# charger.net
KiCad netlist of a schematic drawn in EAGLE
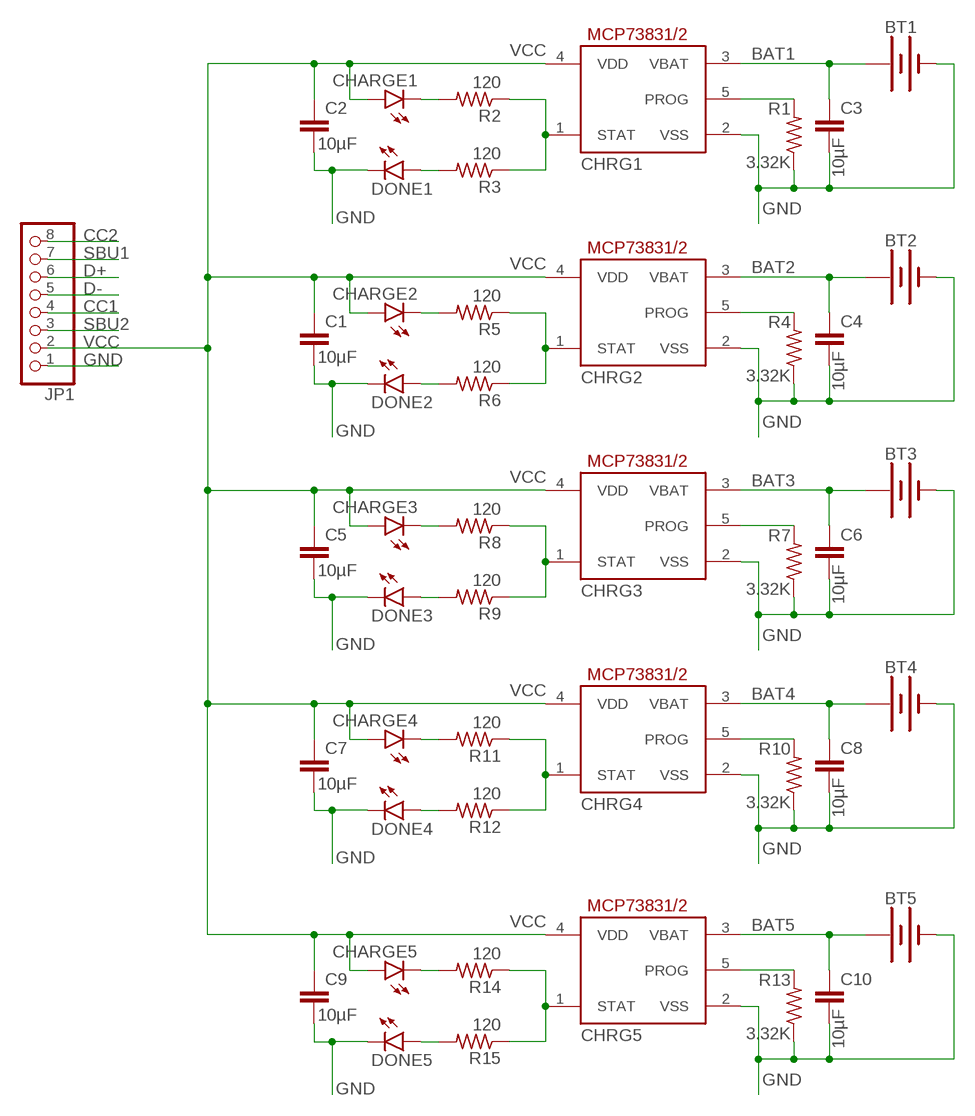
[diagram p0: schematic, sheet 1]

(export (version "E")
  (design (tool "Eeschema 10.0.6"))
  (components
    (comp (ref "BT1")
      (value "BATTERY-18650")
      (footprint "eagle-import:BATTERY_18650-HOLDER")
      (libsource (lib "eagle-import") (part "BATTERY-18650"))
    )
    (comp (ref "BT2")
      (value "BATTERY-18650")
      (footprint "eagle-import:BATTERY_18650-HOLDER")
      (libsource (lib "eagle-import") (part "BATTERY-18650"))
    )
    (comp (ref "BT3")
      (value "BATTERY-18650")
      (footprint "eagle-import:BATTERY_18650-HOLDER")
      (libsource (lib "eagle-import") (part "BATTERY-18650"))
    )
    (comp (ref "BT4")
      (value "BATTERY-18650")
      (footprint "eagle-import:BATTERY_18650-HOLDER")
      (libsource (lib "eagle-import") (part "BATTERY-18650"))
    )
    (comp (ref "BT5")
      (value "BATTERY-18650")
      (footprint "eagle-import:BATTERY_18650-HOLDER")
      (libsource (lib "eagle-import") (part "BATTERY-18650"))
    )
    (comp (ref "C1")
      (value "10µF")
      (footprint "eagle-import:C1206")
      (libsource (lib "eagle-import") (part "C-EUC1206"))
    )
    (comp (ref "C2")
      (value "10µF")
      (footprint "eagle-import:C1206")
      (libsource (lib "eagle-import") (part "C-EUC1206"))
    )
    (comp (ref "C3")
      (value "10µF")
      (footprint "eagle-import:C1206")
      (libsource (lib "eagle-import") (part "C-EUC1206"))
    )
    (comp (ref "C4")
      (value "10µF")
      (footprint "eagle-import:C1206")
      (libsource (lib "eagle-import") (part "C-EUC1206"))
    )
    (comp (ref "C5")
      (value "10µF")
      (footprint "eagle-import:C1206")
      (libsource (lib "eagle-import") (part "C-EUC1206"))
    )
    (comp (ref "C6")
      (value "10µF")
      (footprint "eagle-import:C1206")
      (libsource (lib "eagle-import") (part "C-EUC1206"))
    )
    (comp (ref "C7")
      (value "10µF")
      (footprint "eagle-import:C1206")
      (libsource (lib "eagle-import") (part "C-EUC1206"))
    )
    (comp (ref "C8")
      (value "10µF")
      (footprint "eagle-import:C1206")
      (libsource (lib "eagle-import") (part "C-EUC1206"))
    )
    (comp (ref "C9")
      (value "10µF")
      (footprint "eagle-import:C1206")
      (libsource (lib "eagle-import") (part "C-EUC1206"))
    )
    (comp (ref "C10")
      (value "10µF")
      (footprint "eagle-import:C1206")
      (libsource (lib "eagle-import") (part "C-EUC1206"))
    )
    (comp (ref "CHARGE1")
      (value "LED3MM")
      (footprint "eagle-import:LED3MM")
      (libsource (lib "eagle-import") (part "LED3MM"))
    )
    (comp (ref "CHARGE2")
      (value "LED3MM")
      (footprint "eagle-import:LED3MM")
      (libsource (lib "eagle-import") (part "LED3MM"))
    )
    (comp (ref "CHARGE3")
      (value "LED3MM")
      (footprint "eagle-import:LED3MM")
      (libsource (lib "eagle-import") (part "LED3MM"))
    )
    (comp (ref "CHARGE4")
      (value "LED3MM")
      (footprint "eagle-import:LED3MM")
      (libsource (lib "eagle-import") (part "LED3MM"))
    )
    (comp (ref "CHARGE5")
      (value "LED3MM")
      (footprint "eagle-import:LED3MM")
      (libsource (lib "eagle-import") (part "LED3MM"))
    )
    (comp (ref "CHRG1")
      (value "MCP73831/OT")
      (footprint "eagle-import:SOT23-5L")
      (libsource (lib "eagle-import") (part "MCP73831/OT"))
    )
    (comp (ref "CHRG2")
      (value "MCP73831/OT")
      (footprint "eagle-import:SOT23-5L")
      (libsource (lib "eagle-import") (part "MCP73831/OT"))
    )
    (comp (ref "CHRG3")
      (value "MCP73831/OT")
      (footprint "eagle-import:SOT23-5L")
      (libsource (lib "eagle-import") (part "MCP73831/OT"))
    )
    (comp (ref "CHRG4")
      (value "MCP73831/OT")
      (footprint "eagle-import:SOT23-5L")
      (libsource (lib "eagle-import") (part "MCP73831/OT"))
    )
    (comp (ref "CHRG5")
      (value "MCP73831/OT")
      (footprint "eagle-import:SOT23-5L")
      (libsource (lib "eagle-import") (part "MCP73831/OT"))
    )
    (comp (ref "DONE1")
      (value "LED3MM")
      (footprint "eagle-import:LED3MM")
      (libsource (lib "eagle-import") (part "LED3MM"))
    )
    (comp (ref "DONE2")
      (value "LED3MM")
      (footprint "eagle-import:LED3MM")
      (libsource (lib "eagle-import") (part "LED3MM"))
    )
    (comp (ref "DONE3")
      (value "LED3MM")
      (footprint "eagle-import:LED3MM")
      (libsource (lib "eagle-import") (part "LED3MM"))
    )
    (comp (ref "DONE4")
      (value "LED3MM")
      (footprint "eagle-import:LED3MM")
      (libsource (lib "eagle-import") (part "LED3MM"))
    )
    (comp (ref "DONE5")
      (value "LED3MM")
      (footprint "eagle-import:LED3MM")
      (libsource (lib "eagle-import") (part "LED3MM"))
    )
    (comp (ref "JP1")
      (value "PINHD-1X8CLEANBIG")
      (footprint "eagle-import:1X08-CLEANBIG")
      (libsource (lib "eagle-import") (part "PINHD-1X8CLEANBIG"))
    )
    (comp (ref "R1")
      (value "3.32K")
      (footprint "eagle-import:R1206")
      (libsource (lib "eagle-import") (part "R-US_R1206"))
    )
    (comp (ref "R2")
      (value "120")
      (footprint "eagle-import:R1206")
      (libsource (lib "eagle-import") (part "R-US_R1206"))
    )
    (comp (ref "R3")
      (value "120")
      (footprint "eagle-import:R1206")
      (libsource (lib "eagle-import") (part "R-US_R1206"))
    )
    (comp (ref "R4")
      (value "3.32K")
      (footprint "eagle-import:R1206")
      (libsource (lib "eagle-import") (part "R-US_R1206"))
    )
    (comp (ref "R5")
      (value "120")
      (footprint "eagle-import:R1206")
      (libsource (lib "eagle-import") (part "R-US_R1206"))
    )
    (comp (ref "R6")
      (value "120")
      (footprint "eagle-import:R1206")
      (libsource (lib "eagle-import") (part "R-US_R1206"))
    )
    (comp (ref "R7")
      (value "3.32K")
      (footprint "eagle-import:R1206")
      (libsource (lib "eagle-import") (part "R-US_R1206"))
    )
    (comp (ref "R8")
      (value "120")
      (footprint "eagle-import:R1206")
      (libsource (lib "eagle-import") (part "R-US_R1206"))
    )
    (comp (ref "R9")
      (value "120")
      (footprint "eagle-import:R1206")
      (libsource (lib "eagle-import") (part "R-US_R1206"))
    )
    (comp (ref "R10")
      (value "3.32K")
      (footprint "eagle-import:R1206")
      (libsource (lib "eagle-import") (part "R-US_R1206"))
    )
    (comp (ref "R11")
      (value "120")
      (footprint "eagle-import:R1206")
      (libsource (lib "eagle-import") (part "R-US_R1206"))
    )
    (comp (ref "R12")
      (value "120")
      (footprint "eagle-import:R1206")
      (libsource (lib "eagle-import") (part "R-US_R1206"))
    )
    (comp (ref "R13")
      (value "3.32K")
      (footprint "eagle-import:R1206")
      (libsource (lib "eagle-import") (part "R-US_R1206"))
    )
    (comp (ref "R14")
      (value "120")
      (footprint "eagle-import:R1206")
      (libsource (lib "eagle-import") (part "R-US_R1206"))
    )
    (comp (ref "R15")
      (value "120")
      (footprint "eagle-import:R1206")
      (libsource (lib "eagle-import") (part "R-US_R1206"))
    )
  )
  (nets
    (net (code "1") (name "/BAT1") (class "Default")
      (node (ref "BT1") (pin "PWR@1") (pinfunction "+_PWR@1") (pintype "power_in"))
      (node (ref "BT1") (pin "PWR@2") (pinfunction "+_PWR@2") (pintype "power_in"))
      (node (ref "BT1") (pin "PWR@3") (pinfunction "+_PWR@3") (pintype "power_in"))
      (node (ref "C3") (pin "1") (pinfunction "1_1") (pintype "passive"))
      (node (ref "CHRG1") (pin "3") (pinfunction "VBAT_3") (pintype "bidirectional"))
    )
    (net (code "2") (name "/BAT2") (class "Default")
      (node (ref "BT2") (pin "PWR@1") (pinfunction "+_PWR@1") (pintype "power_in"))
      (node (ref "BT2") (pin "PWR@2") (pinfunction "+_PWR@2") (pintype "power_in"))
      (node (ref "BT2") (pin "PWR@3") (pinfunction "+_PWR@3") (pintype "power_in"))
      (node (ref "C4") (pin "1") (pinfunction "1_1") (pintype "passive"))
      (node (ref "CHRG2") (pin "3") (pinfunction "VBAT_3") (pintype "bidirectional"))
    )
    (net (code "3") (name "/BAT3") (class "Default")
      (node (ref "BT3") (pin "PWR@1") (pinfunction "+_PWR@1") (pintype "power_in"))
      (node (ref "BT3") (pin "PWR@2") (pinfunction "+_PWR@2") (pintype "power_in"))
      (node (ref "BT3") (pin "PWR@3") (pinfunction "+_PWR@3") (pintype "power_in"))
      (node (ref "C6") (pin "1") (pinfunction "1_1") (pintype "passive"))
      (node (ref "CHRG3") (pin "3") (pinfunction "VBAT_3") (pintype "bidirectional"))
    )
    (net (code "4") (name "/BAT4") (class "Default")
      (node (ref "BT4") (pin "PWR@1") (pinfunction "+_PWR@1") (pintype "power_in"))
      (node (ref "BT4") (pin "PWR@2") (pinfunction "+_PWR@2") (pintype "power_in"))
      (node (ref "BT4") (pin "PWR@3") (pinfunction "+_PWR@3") (pintype "power_in"))
      (node (ref "C8") (pin "1") (pinfunction "1_1") (pintype "passive"))
      (node (ref "CHRG4") (pin "3") (pinfunction "VBAT_3") (pintype "bidirectional"))
    )
    (net (code "5") (name "/BAT5") (class "Default")
      (node (ref "BT5") (pin "PWR@1") (pinfunction "+_PWR@1") (pintype "power_in"))
      (node (ref "BT5") (pin "PWR@2") (pinfunction "+_PWR@2") (pintype "power_in"))
      (node (ref "BT5") (pin "PWR@3") (pinfunction "+_PWR@3") (pintype "power_in"))
      (node (ref "C10") (pin "1") (pinfunction "1_1") (pintype "passive"))
      (node (ref "CHRG5") (pin "3") (pinfunction "VBAT_3") (pintype "bidirectional"))
    )
    (net (code "6") (name "/CC1") (class "Default")
      (node (ref "JP1") (pin "4") (pinfunction "4_4") (pintype "passive"))
    )
    (net (code "7") (name "/CC2") (class "Default")
      (node (ref "JP1") (pin "8") (pinfunction "8_8") (pintype "passive"))
    )
    (net (code "8") (name "/D+") (class "Default")
      (node (ref "JP1") (pin "6") (pinfunction "6_6") (pintype "passive"))
    )
    (net (code "9") (name "/D-") (class "Default")
      (node (ref "JP1") (pin "5") (pinfunction "5_5") (pintype "passive"))
    )
    (net (code "10") (name "/GND") (class "Default")
      (node (ref "BT1") (pin "GND@1") (pinfunction "-_GND@1") (pintype "power_in"))
      (node (ref "BT1") (pin "GND@2") (pinfunction "-_GND@2") (pintype "power_in"))
      (node (ref "BT1") (pin "GND@3") (pinfunction "-_GND@3") (pintype "power_in"))
      (node (ref "BT2") (pin "GND@1") (pinfunction "-_GND@1") (pintype "power_in"))
      (node (ref "BT2") (pin "GND@2") (pinfunction "-_GND@2") (pintype "power_in"))
      (node (ref "BT2") (pin "GND@3") (pinfunction "-_GND@3") (pintype "power_in"))
      (node (ref "BT3") (pin "GND@1") (pinfunction "-_GND@1") (pintype "power_in"))
      (node (ref "BT3") (pin "GND@2") (pinfunction "-_GND@2") (pintype "power_in"))
      (node (ref "BT3") (pin "GND@3") (pinfunction "-_GND@3") (pintype "power_in"))
      (node (ref "BT4") (pin "GND@1") (pinfunction "-_GND@1") (pintype "power_in"))
      (node (ref "BT4") (pin "GND@2") (pinfunction "-_GND@2") (pintype "power_in"))
      (node (ref "BT4") (pin "GND@3") (pinfunction "-_GND@3") (pintype "power_in"))
      (node (ref "BT5") (pin "GND@1") (pinfunction "-_GND@1") (pintype "power_in"))
      (node (ref "BT5") (pin "GND@2") (pinfunction "-_GND@2") (pintype "power_in"))
      (node (ref "BT5") (pin "GND@3") (pinfunction "-_GND@3") (pintype "power_in"))
      (node (ref "C1") (pin "2") (pinfunction "2_2") (pintype "passive"))
      (node (ref "C10") (pin "2") (pinfunction "2_2") (pintype "passive"))
      (node (ref "C2") (pin "2") (pinfunction "2_2") (pintype "passive"))
      (node (ref "C3") (pin "2") (pinfunction "2_2") (pintype "passive"))
      (node (ref "C4") (pin "2") (pinfunction "2_2") (pintype "passive"))
      (node (ref "C5") (pin "2") (pinfunction "2_2") (pintype "passive"))
      (node (ref "C6") (pin "2") (pinfunction "2_2") (pintype "passive"))
      (node (ref "C7") (pin "2") (pinfunction "2_2") (pintype "passive"))
      (node (ref "C8") (pin "2") (pinfunction "2_2") (pintype "passive"))
      (node (ref "C9") (pin "2") (pinfunction "2_2") (pintype "passive"))
      (node (ref "CHRG1") (pin "2") (pinfunction "VSS_2") (pintype "power_in"))
      (node (ref "CHRG2") (pin "2") (pinfunction "VSS_2") (pintype "power_in"))
      (node (ref "CHRG3") (pin "2") (pinfunction "VSS_2") (pintype "power_in"))
      (node (ref "CHRG4") (pin "2") (pinfunction "VSS_2") (pintype "power_in"))
      (node (ref "CHRG5") (pin "2") (pinfunction "VSS_2") (pintype "power_in"))
      (node (ref "DONE1") (pin "K") (pinfunction "C_K") (pintype "passive"))
      (node (ref "DONE2") (pin "K") (pinfunction "C_K") (pintype "passive"))
      (node (ref "DONE3") (pin "K") (pinfunction "C_K") (pintype "passive"))
      (node (ref "DONE4") (pin "K") (pinfunction "C_K") (pintype "passive"))
      (node (ref "DONE5") (pin "K") (pinfunction "C_K") (pintype "passive"))
      (node (ref "JP1") (pin "1") (pinfunction "1_1") (pintype "passive"))
      (node (ref "R1") (pin "1") (pinfunction "1_1") (pintype "passive"))
      (node (ref "R10") (pin "1") (pinfunction "1_1") (pintype "passive"))
      (node (ref "R13") (pin "1") (pinfunction "1_1") (pintype "passive"))
      (node (ref "R4") (pin "1") (pinfunction "1_1") (pintype "passive"))
      (node (ref "R7") (pin "1") (pinfunction "1_1") (pintype "passive"))
    )
    (net (code "11") (name "/SBU1") (class "Default")
      (node (ref "JP1") (pin "7") (pinfunction "7_7") (pintype "passive"))
    )
    (net (code "12") (name "/SBU2") (class "Default")
      (node (ref "JP1") (pin "3") (pinfunction "3_3") (pintype "passive"))
    )
    (net (code "13") (name "/VCC") (class "Default")
      (node (ref "C1") (pin "1") (pinfunction "1_1") (pintype "passive"))
      (node (ref "C2") (pin "1") (pinfunction "1_1") (pintype "passive"))
      (node (ref "C5") (pin "1") (pinfunction "1_1") (pintype "passive"))
      (node (ref "C7") (pin "1") (pinfunction "1_1") (pintype "passive"))
      (node (ref "C9") (pin "1") (pinfunction "1_1") (pintype "passive"))
      (node (ref "CHARGE1") (pin "A") (pinfunction "A_A") (pintype "passive"))
      (node (ref "CHARGE2") (pin "A") (pinfunction "A_A") (pintype "passive"))
      (node (ref "CHARGE3") (pin "A") (pinfunction "A_A") (pintype "passive"))
      (node (ref "CHARGE4") (pin "A") (pinfunction "A_A") (pintype "passive"))
      (node (ref "CHARGE5") (pin "A") (pinfunction "A_A") (pintype "passive"))
      (node (ref "CHRG1") (pin "4") (pinfunction "VDD_4") (pintype "power_in"))
      (node (ref "CHRG2") (pin "4") (pinfunction "VDD_4") (pintype "power_in"))
      (node (ref "CHRG3") (pin "4") (pinfunction "VDD_4") (pintype "power_in"))
      (node (ref "CHRG4") (pin "4") (pinfunction "VDD_4") (pintype "power_in"))
      (node (ref "CHRG5") (pin "4") (pinfunction "VDD_4") (pintype "power_in"))
      (node (ref "JP1") (pin "2") (pinfunction "2_2") (pintype "passive"))
    )
    (net (code "14") (name "Net-(CHARGE1-C)") (class "Default")
      (node (ref "CHARGE1") (pin "K") (pinfunction "C_K") (pintype "passive"))
      (node (ref "R2") (pin "2") (pinfunction "2_2") (pintype "passive"))
    )
    (net (code "15") (name "Net-(CHARGE2-C)") (class "Default")
      (node (ref "CHARGE2") (pin "K") (pinfunction "C_K") (pintype "passive"))
      (node (ref "R5") (pin "2") (pinfunction "2_2") (pintype "passive"))
    )
    (net (code "16") (name "Net-(CHARGE3-C)") (class "Default")
      (node (ref "CHARGE3") (pin "K") (pinfunction "C_K") (pintype "passive"))
      (node (ref "R8") (pin "2") (pinfunction "2_2") (pintype "passive"))
    )
    (net (code "17") (name "Net-(CHARGE4-C)") (class "Default")
      (node (ref "CHARGE4") (pin "K") (pinfunction "C_K") (pintype "passive"))
      (node (ref "R11") (pin "2") (pinfunction "2_2") (pintype "passive"))
    )
    (net (code "18") (name "Net-(CHARGE5-C)") (class "Default")
      (node (ref "CHARGE5") (pin "K") (pinfunction "C_K") (pintype "passive"))
      (node (ref "R14") (pin "2") (pinfunction "2_2") (pintype "passive"))
    )
    (net (code "19") (name "Net-(CHRG1-PROG)") (class "Default")
      (node (ref "CHRG1") (pin "5") (pinfunction "PROG_5") (pintype "input"))
      (node (ref "R1") (pin "2") (pinfunction "2_2") (pintype "passive"))
    )
    (net (code "20") (name "Net-(CHRG1-STAT)") (class "Default")
      (node (ref "CHRG1") (pin "1") (pinfunction "STAT_1") (pintype "output"))
      (node (ref "R2") (pin "1") (pinfunction "1_1") (pintype "passive"))
      (node (ref "R3") (pin "1") (pinfunction "1_1") (pintype "passive"))
    )
    (net (code "21") (name "Net-(CHRG2-PROG)") (class "Default")
      (node (ref "CHRG2") (pin "5") (pinfunction "PROG_5") (pintype "input"))
      (node (ref "R4") (pin "2") (pinfunction "2_2") (pintype "passive"))
    )
    (net (code "22") (name "Net-(CHRG2-STAT)") (class "Default")
      (node (ref "CHRG2") (pin "1") (pinfunction "STAT_1") (pintype "output"))
      (node (ref "R5") (pin "1") (pinfunction "1_1") (pintype "passive"))
      (node (ref "R6") (pin "1") (pinfunction "1_1") (pintype "passive"))
    )
    (net (code "23") (name "Net-(CHRG3-PROG)") (class "Default")
      (node (ref "CHRG3") (pin "5") (pinfunction "PROG_5") (pintype "input"))
      (node (ref "R7") (pin "2") (pinfunction "2_2") (pintype "passive"))
    )
    (net (code "24") (name "Net-(CHRG3-STAT)") (class "Default")
      (node (ref "CHRG3") (pin "1") (pinfunction "STAT_1") (pintype "output"))
      (node (ref "R8") (pin "1") (pinfunction "1_1") (pintype "passive"))
      (node (ref "R9") (pin "1") (pinfunction "1_1") (pintype "passive"))
    )
    (net (code "25") (name "Net-(CHRG4-PROG)") (class "Default")
      (node (ref "CHRG4") (pin "5") (pinfunction "PROG_5") (pintype "input"))
      (node (ref "R10") (pin "2") (pinfunction "2_2") (pintype "passive"))
    )
    (net (code "26") (name "Net-(CHRG4-STAT)") (class "Default")
      (node (ref "CHRG4") (pin "1") (pinfunction "STAT_1") (pintype "output"))
      (node (ref "R11") (pin "1") (pinfunction "1_1") (pintype "passive"))
      (node (ref "R12") (pin "1") (pinfunction "1_1") (pintype "passive"))
    )
    (net (code "27") (name "Net-(CHRG5-PROG)") (class "Default")
      (node (ref "CHRG5") (pin "5") (pinfunction "PROG_5") (pintype "input"))
      (node (ref "R13") (pin "2") (pinfunction "2_2") (pintype "passive"))
    )
    (net (code "28") (name "Net-(CHRG5-STAT)") (class "Default")
      (node (ref "CHRG5") (pin "1") (pinfunction "STAT_1") (pintype "output"))
      (node (ref "R14") (pin "1") (pinfunction "1_1") (pintype "passive"))
      (node (ref "R15") (pin "1") (pinfunction "1_1") (pintype "passive"))
    )
    (net (code "29") (name "Net-(DONE1-PadA)") (class "Default")
      (node (ref "DONE1") (pin "A") (pinfunction "A_A") (pintype "passive"))
      (node (ref "R3") (pin "2") (pinfunction "2_2") (pintype "passive"))
    )
    (net (code "30") (name "Net-(DONE2-PadA)") (class "Default")
      (node (ref "DONE2") (pin "A") (pinfunction "A_A") (pintype "passive"))
      (node (ref "R6") (pin "2") (pinfunction "2_2") (pintype "passive"))
    )
    (net (code "31") (name "Net-(DONE3-PadA)") (class "Default")
      (node (ref "DONE3") (pin "A") (pinfunction "A_A") (pintype "passive"))
      (node (ref "R9") (pin "2") (pinfunction "2_2") (pintype "passive"))
    )
    (net (code "32") (name "Net-(DONE4-PadA)") (class "Default")
      (node (ref "DONE4") (pin "A") (pinfunction "A_A") (pintype "passive"))
      (node (ref "R12") (pin "2") (pinfunction "2_2") (pintype "passive"))
    )
    (net (code "33") (name "Net-(DONE5-PadA)") (class "Default")
      (node (ref "DONE5") (pin "A") (pinfunction "A_A") (pintype "passive"))
      (node (ref "R15") (pin "2") (pinfunction "2_2") (pintype "passive"))
    )
  )
)
